# pad_2025-11-01.net
KiCad netlist of a schematic drawn in EasyEDA Pro
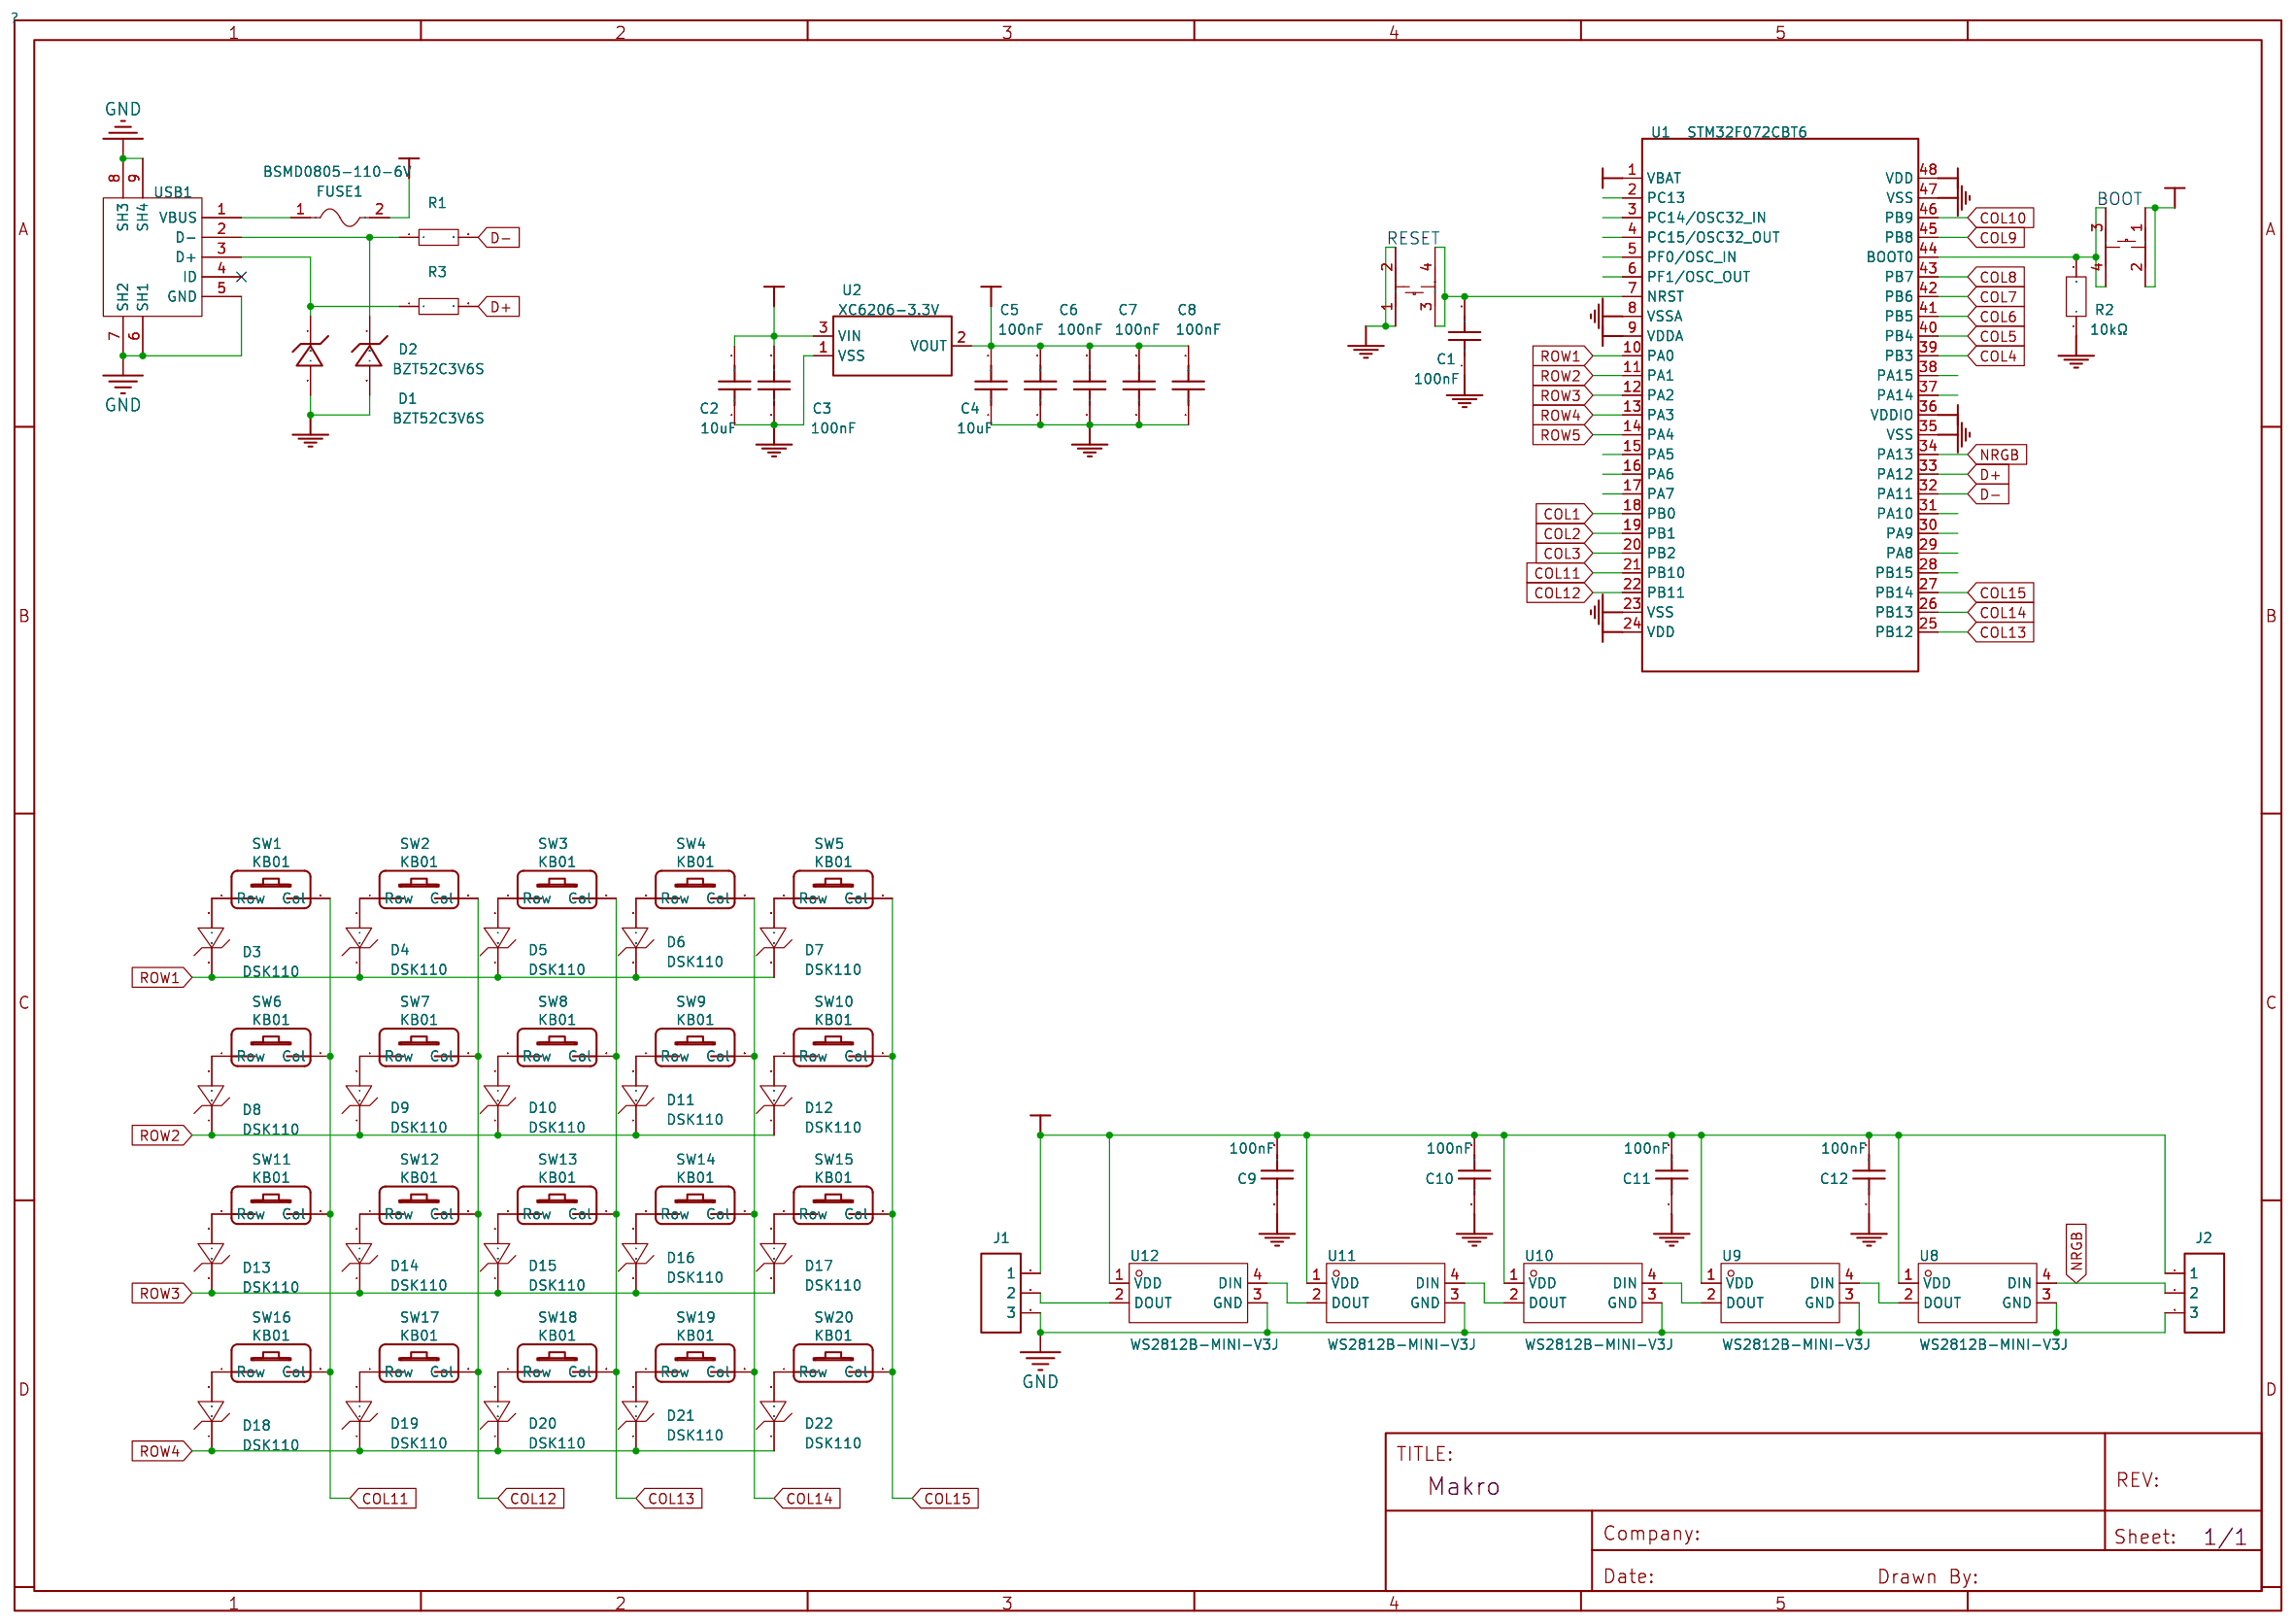
[diagram p0: schematic sheet]

(export (version "E")
  (design (tool "Eeschema 10.0.6"))
  (components
    (comp (ref "C1")
      (value "100nF")
      (fields
        (field (name "Manufacturer Part") "CC0805KKX7R0BB104")
        (field (name "Manufacturer") "YAGEO(国巨)")
      )
      (libsource (lib "easyedapro") (part "0.1uF"))
    )
    (comp (ref "C2")
      (value "10uF")
      (description "Capacitance:10uF Tolerance:±10% Tolerance:±10% Voltage Rating:6.3V Temperature Coefficient:X7R")
      (fields
        (field (name "Manufacturer Part") "CL21B106KQQNNNE")
        (field (name "Manufacturer") "SAMSUNG(三星)")
      )
      (libsource (lib "easyedapro") (part "10u"))
    )
    (comp (ref "C3")
      (value "100nF")
      (fields
        (field (name "Manufacturer Part") "CC0805KKX7R0BB104")
        (field (name "Manufacturer") "YAGEO(国巨)")
      )
      (libsource (lib "") (part "0.1uF_1"))
    )
    (comp (ref "C4")
      (value "10uF")
      (description "Capacitance:10uF Tolerance:±10% Tolerance:±10% Voltage Rating:6.3V Temperature Coefficient:X7R")
      (fields
        (field (name "Manufacturer Part") "CL21B106KQQNNNE")
        (field (name "Manufacturer") "SAMSUNG(三星)")
      )
      (libsource (lib "easyedapro") (part "10u"))
    )
    (comp (ref "C5")
      (value "100nF")
      (fields
        (field (name "Manufacturer Part") "CC0805KKX7R0BB104")
        (field (name "Manufacturer") "YAGEO(国巨)")
      )
      (libsource (lib "") (part "0.1uF_1"))
    )
    (comp (ref "C6")
      (value "100nF")
      (fields
        (field (name "Manufacturer Part") "CC0805KKX7R0BB104")
        (field (name "Manufacturer") "YAGEO(国巨)")
      )
      (libsource (lib "") (part "0.1uF_1"))
    )
    (comp (ref "C7")
      (value "100nF")
      (fields
        (field (name "Manufacturer Part") "CC0805KKX7R0BB104")
        (field (name "Manufacturer") "YAGEO(国巨)")
      )
      (libsource (lib "") (part "0.1uF_1"))
    )
    (comp (ref "C8")
      (value "100nF")
      (fields
        (field (name "Manufacturer Part") "CC0805KKX7R0BB104")
        (field (name "Manufacturer") "YAGEO(国巨)")
      )
      (libsource (lib "") (part "0.1uF_1"))
    )
    (comp (ref "C9")
      (value "100nF")
      (fields
        (field (name "Manufacturer Part") "CC0805KKX7R0BB104")
        (field (name "Manufacturer") "YAGEO(国巨)")
      )
      (libsource (lib "easyedapro") (part "0.1uF"))
    )
    (comp (ref "C10")
      (value "100nF")
      (fields
        (field (name "Manufacturer Part") "CC0805KKX7R0BB104")
        (field (name "Manufacturer") "YAGEO(国巨)")
      )
      (libsource (lib "easyedapro") (part "0.1uF"))
    )
    (comp (ref "C11")
      (value "100nF")
      (fields
        (field (name "Manufacturer Part") "CC0805KKX7R0BB104")
        (field (name "Manufacturer") "YAGEO(国巨)")
      )
      (libsource (lib "easyedapro") (part "0.1uF"))
    )
    (comp (ref "C12")
      (value "100nF")
      (fields
        (field (name "Manufacturer Part") "CC0805KKX7R0BB104")
        (field (name "Manufacturer") "YAGEO(国巨)")
      )
      (libsource (lib "easyedapro") (part "0.1uF"))
    )
    (comp (ref "D1")
      (value "BZT52C3V6S")
      (fields (field (name "Manufacturer") "CBI(创基)"))
      (libsource (lib "easyedapro") (part "ZMM3V6"))
    )
    (comp (ref "D2")
      (value "BZT52C3V6S")
      (fields (field (name "Manufacturer") "CBI(创基)"))
      (libsource (lib "easyedapro") (part "ZMM3V6"))
    )
    (comp (ref "D3")
      (value "DSK110")
      (footprint "easyedapro:SOD-123FL_L2.7-W1.8-LS3.8-RD")
      (fields (field (name "Manufacturer") "GOODWORK(固得沃克)"))
      (libsource (lib "easyedapro") (part "DSK110_C41371069"))
    )
    (comp (ref "D4")
      (value "DSK110")
      (footprint "easyedapro:SOD-123FL_L2.7-W1.8-LS3.8-RD")
      (fields (field (name "Manufacturer") "GOODWORK(固得沃克)"))
      (libsource (lib "easyedapro") (part "DSK110_C41371069"))
    )
    (comp (ref "D5")
      (value "DSK110")
      (footprint "easyedapro:SOD-123FL_L2.7-W1.8-LS3.8-RD")
      (fields (field (name "Manufacturer") "GOODWORK(固得沃克)"))
      (libsource (lib "easyedapro") (part "DSK110_C41371069"))
    )
    (comp (ref "D6")
      (value "DSK110")
      (footprint "easyedapro:SOD-123FL_L2.7-W1.8-LS3.8-RD")
      (fields (field (name "Manufacturer") "GOODWORK(固得沃克)"))
      (libsource (lib "easyedapro") (part "DSK110_C41371069"))
    )
    (comp (ref "D7")
      (value "DSK110")
      (footprint "easyedapro:SOD-123FL_L2.7-W1.8-LS3.8-RD")
      (fields (field (name "Manufacturer") "GOODWORK(固得沃克)"))
      (libsource (lib "easyedapro") (part "DSK110_C41371069"))
    )
    (comp (ref "D8")
      (value "DSK110")
      (footprint "easyedapro:SOD-123FL_L2.7-W1.8-LS3.8-RD")
      (fields (field (name "Manufacturer") "GOODWORK(固得沃克)"))
      (libsource (lib "easyedapro") (part "DSK110_C41371069"))
    )
    (comp (ref "D9")
      (value "DSK110")
      (footprint "easyedapro:SOD-123FL_L2.7-W1.8-LS3.8-RD")
      (fields (field (name "Manufacturer") "GOODWORK(固得沃克)"))
      (libsource (lib "easyedapro") (part "DSK110_C41371069"))
    )
    (comp (ref "D10")
      (value "DSK110")
      (footprint "easyedapro:SOD-123FL_L2.7-W1.8-LS3.8-RD")
      (fields (field (name "Manufacturer") "GOODWORK(固得沃克)"))
      (libsource (lib "easyedapro") (part "DSK110_C41371069"))
    )
    (comp (ref "D11")
      (value "DSK110")
      (footprint "easyedapro:SOD-123FL_L2.7-W1.8-LS3.8-RD")
      (fields (field (name "Manufacturer") "GOODWORK(固得沃克)"))
      (libsource (lib "easyedapro") (part "DSK110_C41371069"))
    )
    (comp (ref "D12")
      (value "DSK110")
      (footprint "easyedapro:SOD-123FL_L2.7-W1.8-LS3.8-RD")
      (fields (field (name "Manufacturer") "GOODWORK(固得沃克)"))
      (libsource (lib "easyedapro") (part "DSK110_C41371069"))
    )
    (comp (ref "D13")
      (value "DSK110")
      (footprint "easyedapro:SOD-123FL_L2.7-W1.8-LS3.8-RD")
      (fields (field (name "Manufacturer") "GOODWORK(固得沃克)"))
      (libsource (lib "easyedapro") (part "DSK110_C41371069"))
    )
    (comp (ref "D14")
      (value "DSK110")
      (footprint "easyedapro:SOD-123FL_L2.7-W1.8-LS3.8-RD")
      (fields (field (name "Manufacturer") "GOODWORK(固得沃克)"))
      (libsource (lib "easyedapro") (part "DSK110_C41371069"))
    )
    (comp (ref "D15")
      (value "DSK110")
      (footprint "easyedapro:SOD-123FL_L2.7-W1.8-LS3.8-RD")
      (fields (field (name "Manufacturer") "GOODWORK(固得沃克)"))
      (libsource (lib "easyedapro") (part "DSK110_C41371069"))
    )
    (comp (ref "D16")
      (value "DSK110")
      (footprint "easyedapro:SOD-123FL_L2.7-W1.8-LS3.8-RD")
      (fields (field (name "Manufacturer") "GOODWORK(固得沃克)"))
      (libsource (lib "easyedapro") (part "DSK110_C41371069"))
    )
    (comp (ref "D17")
      (value "DSK110")
      (footprint "easyedapro:SOD-123FL_L2.7-W1.8-LS3.8-RD")
      (fields (field (name "Manufacturer") "GOODWORK(固得沃克)"))
      (libsource (lib "easyedapro") (part "DSK110_C41371069"))
    )
    (comp (ref "D18")
      (value "DSK110")
      (footprint "easyedapro:SOD-123FL_L2.7-W1.8-LS3.8-RD")
      (fields (field (name "Manufacturer") "GOODWORK(固得沃克)"))
      (libsource (lib "easyedapro") (part "DSK110_C41371069"))
    )
    (comp (ref "D19")
      (value "DSK110")
      (footprint "easyedapro:SOD-123FL_L2.7-W1.8-LS3.8-RD")
      (fields (field (name "Manufacturer") "GOODWORK(固得沃克)"))
      (libsource (lib "easyedapro") (part "DSK110_C41371069"))
    )
    (comp (ref "D20")
      (value "DSK110")
      (footprint "easyedapro:SOD-123FL_L2.7-W1.8-LS3.8-RD")
      (fields (field (name "Manufacturer") "GOODWORK(固得沃克)"))
      (libsource (lib "easyedapro") (part "DSK110_C41371069"))
    )
    (comp (ref "D21")
      (value "DSK110")
      (footprint "easyedapro:SOD-123FL_L2.7-W1.8-LS3.8-RD")
      (fields (field (name "Manufacturer") "GOODWORK(固得沃克)"))
      (libsource (lib "easyedapro") (part "DSK110_C41371069"))
    )
    (comp (ref "D22")
      (value "DSK110")
      (footprint "easyedapro:SOD-123FL_L2.7-W1.8-LS3.8-RD")
      (fields (field (name "Manufacturer") "GOODWORK(固得沃克)"))
      (libsource (lib "easyedapro") (part "DSK110_C41371069"))
    )
    (comp (ref "FUSE1")
      (value "BSMD0805-110-6V")
      (footprint "easyedapro:F0805")
      (fields (field (name "Manufacturer") "BHFUSE(佰宏)"))
      (libsource (lib "easyedapro") (part "BSMD0805-110-6V"))
    )
    (comp (ref "J1") (value "77311-102-03LF") (libsource (lib "") (part "Pin03_1")))
    (comp (ref "J2") (value "77311-102-03LF") (libsource (lib "easyedapro") (part "Pin03")))
    (comp (ref "KEY1")
      (value "TS-1187A-C-B-B")
      (footprint "easyedapro:SW-SMD_4P-L5.1-W5.1-P3.70-LS6.5-TL_H1.6")
      (fields (field (name "Manufacturer") "XKB Connectivity(中国星坤)"))
      (libsource (lib "easyedapro") (part "TS-1187A-C-B-B"))
    )
    (comp (ref "KEY2")
      (value "TS-1187A-C-B-B")
      (footprint "easyedapro:SW-SMD_4P-L5.1-W5.1-P3.70-LS6.5-TL_H1.6")
      (fields (field (name "Manufacturer") "XKB Connectivity(中国星坤)"))
      (libsource (lib "easyedapro") (part "TS-1187A-C-B-B"))
    )
    (comp (ref "R1")
      (value "22Ω")
      (footprint "easyedapro:R0805")
      (fields
        (field (name "Manufacturer Part") "0805W8F220JT5E")
        (field (name "Manufacturer") "UNI-ROYAL(厚声)")
      )
      (libsource (lib "easyedapro") (part "0805W8F220JT5E"))
    )
    (comp (ref "R2")
      (value "10kΩ")
      (footprint "easyedapro:R0805")
      (fields (field (name "Manufacturer Part") "FRC0805J103TS") (field (name "Manufacturer") "FOJAN(富捷)"))
      (libsource (lib "easyedapro") (part "FRC0805J103TS"))
    )
    (comp (ref "R3")
      (value "22Ω")
      (footprint "easyedapro:R0805")
      (fields
        (field (name "Manufacturer Part") "0805W8F220JT5E")
        (field (name "Manufacturer") "UNI-ROYAL(厚声)")
      )
      (libsource (lib "easyedapro") (part "0805W8F220JT5E"))
    )
    (comp (ref "SW1")
      (value "KB01")
      (fields (field (name "Manufacturer Part") "00") (field (name "Contributor") "Citiclzy"))
      (libsource (lib "easyedapro") (part "KB01"))
    )
    (comp (ref "SW2")
      (value "KB01")
      (fields (field (name "Manufacturer Part") "00") (field (name "Contributor") "Citiclzy"))
      (libsource (lib "easyedapro") (part "KB01"))
    )
    (comp (ref "SW3")
      (value "KB01")
      (fields (field (name "Manufacturer Part") "00") (field (name "Contributor") "Citiclzy"))
      (libsource (lib "easyedapro") (part "KB01"))
    )
    (comp (ref "SW4")
      (value "KB01")
      (fields (field (name "Manufacturer Part") "00") (field (name "Contributor") "Citiclzy"))
      (libsource (lib "easyedapro") (part "KB01"))
    )
    (comp (ref "SW5")
      (value "KB01")
      (fields (field (name "Manufacturer Part") "00") (field (name "Contributor") "Citiclzy"))
      (libsource (lib "easyedapro") (part "KB01"))
    )
    (comp (ref "SW6")
      (value "KB01")
      (fields (field (name "Manufacturer Part") "00") (field (name "Contributor") "Citiclzy"))
      (libsource (lib "easyedapro") (part "KB01"))
    )
    (comp (ref "SW7")
      (value "KB01")
      (fields (field (name "Manufacturer Part") "00") (field (name "Contributor") "Citiclzy"))
      (libsource (lib "easyedapro") (part "KB01"))
    )
    (comp (ref "SW8")
      (value "KB01")
      (fields (field (name "Manufacturer Part") "00") (field (name "Contributor") "Citiclzy"))
      (libsource (lib "easyedapro") (part "KB01"))
    )
    (comp (ref "SW9")
      (value "KB01")
      (fields (field (name "Manufacturer Part") "00") (field (name "Contributor") "Citiclzy"))
      (libsource (lib "easyedapro") (part "KB01"))
    )
    (comp (ref "SW10")
      (value "KB01")
      (fields (field (name "Manufacturer Part") "00") (field (name "Contributor") "Citiclzy"))
      (libsource (lib "easyedapro") (part "KB01"))
    )
    (comp (ref "SW11")
      (value "KB01")
      (fields (field (name "Manufacturer Part") "00") (field (name "Contributor") "Citiclzy"))
      (libsource (lib "easyedapro") (part "KB01"))
    )
    (comp (ref "SW12")
      (value "KB01")
      (fields (field (name "Manufacturer Part") "00") (field (name "Contributor") "Citiclzy"))
      (libsource (lib "easyedapro") (part "KB01"))
    )
    (comp (ref "SW13")
      (value "KB01")
      (fields (field (name "Manufacturer Part") "00") (field (name "Contributor") "Citiclzy"))
      (libsource (lib "easyedapro") (part "KB01"))
    )
    (comp (ref "SW14")
      (value "KB01")
      (fields (field (name "Manufacturer Part") "00") (field (name "Contributor") "Citiclzy"))
      (libsource (lib "easyedapro") (part "KB01"))
    )
    (comp (ref "SW15")
      (value "KB01")
      (fields (field (name "Manufacturer Part") "00") (field (name "Contributor") "Citiclzy"))
      (libsource (lib "easyedapro") (part "KB01"))
    )
    (comp (ref "SW16")
      (value "KB01")
      (fields (field (name "Manufacturer Part") "00") (field (name "Contributor") "Citiclzy"))
      (libsource (lib "easyedapro") (part "KB01"))
    )
    (comp (ref "SW17")
      (value "KB01")
      (fields (field (name "Manufacturer Part") "00") (field (name "Contributor") "Citiclzy"))
      (libsource (lib "easyedapro") (part "KB01"))
    )
    (comp (ref "SW18")
      (value "KB01")
      (fields (field (name "Manufacturer Part") "00") (field (name "Contributor") "Citiclzy"))
      (libsource (lib "easyedapro") (part "KB01"))
    )
    (comp (ref "SW19")
      (value "KB01")
      (fields (field (name "Manufacturer Part") "00") (field (name "Contributor") "Citiclzy"))
      (libsource (lib "easyedapro") (part "KB01"))
    )
    (comp (ref "SW20")
      (value "KB01")
      (fields (field (name "Manufacturer Part") "00") (field (name "Contributor") "Citiclzy"))
      (libsource (lib "easyedapro") (part "KB01"))
    )
    (comp (ref "U1")
      (value "STM32F072CBT6")
      (footprint "easyedapro:LQFP-48_L7.0-W7.0-P0.50-LS9.0-BL")
      (fields (field (name "Manufacturer") "ST(意法半导体)"))
      (libsource (lib "easyedapro") (part "STM32F072CBT6"))
    )
    (comp (ref "U2")
      (value "XC6206-3.3V")
      (footprint "easyedapro:SSOT-3_L2.9-W1.6-P0.95-LS2.8-BR")
      (fields (field (name "Manufacturer") "YONGYUTAI(永裕泰)") (field (name "Contributor") "LCSC"))
      (libsource (lib "easyedapro") (part "XC6206-3.3V"))
    )
    (comp (ref "U8")
      (value "WS2812B-MINI-V3J")
      (footprint "easyedapro:LED-SMD_4P-L3.5-W3.5-P1.80-LS6.2_WS2812B-MINI-V3J")
      (fields (field (name "Manufacturer") "worldsemi"))
      (libsource (lib "easyedapro") (part "WS2812B-MINI-V3J"))
    )
    (comp (ref "U9")
      (value "WS2812B-MINI-V3J")
      (footprint "easyedapro:LED-SMD_4P-L3.5-W3.5-P1.80-LS6.2_WS2812B-MINI-V3J")
      (fields (field (name "Manufacturer") "worldsemi"))
      (libsource (lib "easyedapro") (part "WS2812B-MINI-V3J"))
    )
    (comp (ref "U10")
      (value "WS2812B-MINI-V3J")
      (footprint "easyedapro:LED-SMD_4P-L3.5-W3.5-P1.80-LS6.2_WS2812B-MINI-V3J")
      (fields (field (name "Manufacturer") "worldsemi"))
      (libsource (lib "easyedapro") (part "WS2812B-MINI-V3J"))
    )
    (comp (ref "U11")
      (value "WS2812B-MINI-V3J")
      (footprint "easyedapro:LED-SMD_4P-L3.5-W3.5-P1.80-LS6.2_WS2812B-MINI-V3J")
      (fields (field (name "Manufacturer") "worldsemi"))
      (libsource (lib "easyedapro") (part "WS2812B-MINI-V3J"))
    )
    (comp (ref "U12")
      (value "WS2812B-MINI-V3J")
      (footprint "easyedapro:LED-SMD_4P-L3.5-W3.5-P1.80-LS6.2_WS2812B-MINI-V3J")
      (fields (field (name "Manufacturer") "worldsemi"))
      (libsource (lib "easyedapro") (part "WS2812B-MINI-V3J"))
    )
    (comp (ref "USB1")
      (value "MicroXNJ")
      (footprint "easyedapro:MICRO-USB-SMD_MICROXNJ")
      (fields (field (name "Manufacturer") "SHOU HAN(首韩)"))
      (libsource (lib "easyedapro") (part "MICROXNJ"))
    )
  )
  (nets
    (net (code "1") (name "+3.3V") (class "Default")
      (node (ref "C4") (pin "2") (pinfunction "2_2") (pintype "unspecified"))
      (node (ref "C5") (pin "2") (pinfunction "2_2") (pintype "unspecified"))
      (node (ref "C6") (pin "2") (pinfunction "2_2") (pintype "unspecified"))
      (node (ref "C7") (pin "2") (pinfunction "2_2") (pintype "unspecified"))
      (node (ref "C8") (pin "2") (pinfunction "2_2") (pintype "unspecified"))
      (node (ref "KEY1") (pin "1") (pinfunction "1_1") (pintype "unspecified"))
      (node (ref "KEY1") (pin "2") (pinfunction "2_2") (pintype "unspecified"))
      (node (ref "U1") (pin "1") (pinfunction "VBAT_1") (pintype "unspecified"))
      (node (ref "U1") (pin "24") (pinfunction "VDD_24") (pintype "unspecified"))
      (node (ref "U1") (pin "36") (pinfunction "VDDIO_36") (pintype "unspecified"))
      (node (ref "U1") (pin "48") (pinfunction "VDD_48") (pintype "unspecified"))
      (node (ref "U1") (pin "9") (pinfunction "VDDA_9") (pintype "unspecified"))
      (node (ref "U2") (pin "2") (pinfunction "VOUT_2") (pintype "unspecified"))
    )
    (net (code "2") (name "COL1") (class "Default")
      (node (ref "U1") (pin "18") (pinfunction "PB0_18") (pintype "unspecified"))
    )
    (net (code "3") (name "COL2") (class "Default")
      (node (ref "U1") (pin "19") (pinfunction "PB1_19") (pintype "unspecified"))
    )
    (net (code "4") (name "COL3") (class "Default")
      (node (ref "U1") (pin "20") (pinfunction "PB2_20") (pintype "unspecified"))
    )
    (net (code "5") (name "COL4") (class "Default")
      (node (ref "U1") (pin "39") (pinfunction "PB3_39") (pintype "unspecified"))
    )
    (net (code "6") (name "COL5") (class "Default")
      (node (ref "U1") (pin "40") (pinfunction "PB4_40") (pintype "unspecified"))
    )
    (net (code "7") (name "COL6") (class "Default")
      (node (ref "U1") (pin "41") (pinfunction "PB5_41") (pintype "unspecified"))
    )
    (net (code "8") (name "COL7") (class "Default")
      (node (ref "U1") (pin "42") (pinfunction "PB6_42") (pintype "unspecified"))
    )
    (net (code "9") (name "COL8") (class "Default")
      (node (ref "U1") (pin "43") (pinfunction "PB7_43") (pintype "unspecified"))
    )
    (net (code "10") (name "COL9") (class "Default")
      (node (ref "U1") (pin "45") (pinfunction "PB8_45") (pintype "unspecified"))
    )
    (net (code "11") (name "COL10") (class "Default")
      (node (ref "U1") (pin "46") (pinfunction "PB9_46") (pintype "unspecified"))
    )
    (net (code "12") (name "COL11") (class "Default")
      (node (ref "SW1") (pin "2") (pinfunction "Col_2") (pintype "unspecified"))
      (node (ref "SW11") (pin "2") (pinfunction "Col_2") (pintype "unspecified"))
      (node (ref "SW16") (pin "2") (pinfunction "Col_2") (pintype "unspecified"))
      (node (ref "SW6") (pin "2") (pinfunction "Col_2") (pintype "unspecified"))
      (node (ref "U1") (pin "21") (pinfunction "PB10_21") (pintype "unspecified"))
    )
    (net (code "13") (name "COL12") (class "Default")
      (node (ref "SW12") (pin "2") (pinfunction "Col_2") (pintype "unspecified"))
      (node (ref "SW17") (pin "2") (pinfunction "Col_2") (pintype "unspecified"))
      (node (ref "SW2") (pin "2") (pinfunction "Col_2") (pintype "unspecified"))
      (node (ref "SW7") (pin "2") (pinfunction "Col_2") (pintype "unspecified"))
      (node (ref "U1") (pin "22") (pinfunction "PB11_22") (pintype "unspecified"))
    )
    (net (code "14") (name "COL13") (class "Default")
      (node (ref "SW13") (pin "2") (pinfunction "Col_2") (pintype "unspecified"))
      (node (ref "SW18") (pin "2") (pinfunction "Col_2") (pintype "unspecified"))
      (node (ref "SW3") (pin "2") (pinfunction "Col_2") (pintype "unspecified"))
      (node (ref "SW8") (pin "2") (pinfunction "Col_2") (pintype "unspecified"))
      (node (ref "U1") (pin "25") (pinfunction "PB12_25") (pintype "unspecified"))
    )
    (net (code "15") (name "COL14") (class "Default")
      (node (ref "SW14") (pin "2") (pinfunction "Col_2") (pintype "unspecified"))
      (node (ref "SW19") (pin "2") (pinfunction "Col_2") (pintype "unspecified"))
      (node (ref "SW4") (pin "2") (pinfunction "Col_2") (pintype "unspecified"))
      (node (ref "SW9") (pin "2") (pinfunction "Col_2") (pintype "unspecified"))
      (node (ref "U1") (pin "26") (pinfunction "PB13_26") (pintype "unspecified"))
    )
    (net (code "16") (name "COL15") (class "Default")
      (node (ref "SW10") (pin "2") (pinfunction "Col_2") (pintype "unspecified"))
      (node (ref "SW15") (pin "2") (pinfunction "Col_2") (pintype "unspecified"))
      (node (ref "SW20") (pin "2") (pinfunction "Col_2") (pintype "unspecified"))
      (node (ref "SW5") (pin "2") (pinfunction "Col_2") (pintype "unspecified"))
      (node (ref "U1") (pin "27") (pinfunction "PB14_27") (pintype "unspecified"))
    )
    (net (code "17") (name "D+") (class "Default")
      (node (ref "R3") (pin "2") (pinfunction "2_2") (pintype "input"))
      (node (ref "U1") (pin "33") (pinfunction "PA12_33") (pintype "unspecified"))
    )
    (net (code "18") (name "D-") (class "Default")
      (node (ref "R1") (pin "2") (pinfunction "2_2") (pintype "input"))
      (node (ref "U1") (pin "32") (pinfunction "PA11_32") (pintype "unspecified"))
    )
    (net (code "19") (name "GND") (class "Default")
      (node (ref "C1") (pin "1") (pinfunction "1_1") (pintype "unspecified"))
      (node (ref "C10") (pin "1") (pinfunction "1_1") (pintype "unspecified"))
      (node (ref "C11") (pin "1") (pinfunction "1_1") (pintype "unspecified"))
      (node (ref "C12") (pin "1") (pinfunction "1_1") (pintype "unspecified"))
      (node (ref "C2") (pin "1") (pinfunction "1_1") (pintype "unspecified"))
      (node (ref "C3") (pin "1") (pinfunction "1_1") (pintype "unspecified"))
      (node (ref "C4") (pin "1") (pinfunction "1_1") (pintype "unspecified"))
      (node (ref "C5") (pin "1") (pinfunction "1_1") (pintype "unspecified"))
      (node (ref "C6") (pin "1") (pinfunction "1_1") (pintype "unspecified"))
      (node (ref "C7") (pin "1") (pinfunction "1_1") (pintype "unspecified"))
      (node (ref "C8") (pin "1") (pinfunction "1_1") (pintype "unspecified"))
      (node (ref "C9") (pin "1") (pinfunction "1_1") (pintype "unspecified"))
      (node (ref "D1") (pin "2") (pinfunction "A_2") (pintype "unspecified"))
      (node (ref "D2") (pin "2") (pinfunction "A_2") (pintype "unspecified"))
      (node (ref "J1") (pin "3") (pinfunction "3_3") (pintype "input"))
      (node (ref "J2") (pin "3") (pinfunction "3_3") (pintype "input"))
      (node (ref "KEY2") (pin "1") (pinfunction "1_1") (pintype "unspecified"))
      (node (ref "KEY2") (pin "2") (pinfunction "2_2") (pintype "unspecified"))
      (node (ref "R2") (pin "1") (pinfunction "1_1") (pintype "unspecified"))
      (node (ref "U1") (pin "23") (pinfunction "VSS_23") (pintype "unspecified"))
      (node (ref "U1") (pin "35") (pinfunction "VSS_35") (pintype "unspecified"))
      (node (ref "U1") (pin "47") (pinfunction "VSS_47") (pintype "unspecified"))
      (node (ref "U1") (pin "8") (pinfunction "VSSA_8") (pintype "unspecified"))
      (node (ref "U10") (pin "3") (pinfunction "GND_3") (pintype "unspecified"))
      (node (ref "U11") (pin "3") (pinfunction "GND_3") (pintype "unspecified"))
      (node (ref "U12") (pin "3") (pinfunction "GND_3") (pintype "unspecified"))
      (node (ref "U2") (pin "1") (pinfunction "VSS_1") (pintype "unspecified"))
      (node (ref "U8") (pin "3") (pinfunction "GND_3") (pintype "unspecified"))
      (node (ref "U9") (pin "3") (pinfunction "GND_3") (pintype "unspecified"))
      (node (ref "USB1") (pin "5") (pinfunction "GND_5") (pintype "unspecified"))
      (node (ref "USB1") (pin "6") (pinfunction "SH1_6") (pintype "unspecified"))
      (node (ref "USB1") (pin "7") (pinfunction "SH2_7") (pintype "unspecified"))
      (node (ref "USB1") (pin "8") (pinfunction "SH3_8") (pintype "unspecified"))
      (node (ref "USB1") (pin "9") (pinfunction "SH4_9") (pintype "unspecified"))
    )
    (net (code "20") (name "NRGB") (class "Default")
      (node (ref "J2") (pin "2") (pinfunction "2_2") (pintype "input"))
      (node (ref "U1") (pin "34") (pinfunction "PA13_34") (pintype "unspecified"))
      (node (ref "U8") (pin "4") (pinfunction "DIN_4") (pintype "unspecified"))
    )
    (net (code "21") (name "Net-(D1-C)") (class "Default")
      (node (ref "D1") (pin "1") (pinfunction "C_1") (pintype "unspecified"))
      (node (ref "R3") (pin "1") (pinfunction "1_1") (pintype "input"))
      (node (ref "USB1") (pin "3") (pinfunction "D+_3") (pintype "unspecified"))
    )
    (net (code "22") (name "Net-(D2-C)") (class "Default")
      (node (ref "D2") (pin "1") (pinfunction "C_1") (pintype "unspecified"))
      (node (ref "R1") (pin "1") (pinfunction "1_1") (pintype "input"))
      (node (ref "USB1") (pin "2") (pinfunction "D-_2") (pintype "unspecified"))
    )
    (net (code "23") (name "Net-(D3-A)") (class "Default")
      (node (ref "D3") (pin "2") (pinfunction "A_2") (pintype "unspecified"))
      (node (ref "SW1") (pin "1") (pinfunction "Row_1") (pintype "unspecified"))
    )
    (net (code "24") (name "Net-(D4-A)") (class "Default")
      (node (ref "D4") (pin "2") (pinfunction "A_2") (pintype "unspecified"))
      (node (ref "SW2") (pin "1") (pinfunction "Row_1") (pintype "unspecified"))
    )
    (net (code "25") (name "Net-(D5-A)") (class "Default")
      (node (ref "D5") (pin "2") (pinfunction "A_2") (pintype "unspecified"))
      (node (ref "SW3") (pin "1") (pinfunction "Row_1") (pintype "unspecified"))
    )
    (net (code "26") (name "Net-(D6-A)") (class "Default")
      (node (ref "D6") (pin "2") (pinfunction "A_2") (pintype "unspecified"))
      (node (ref "SW4") (pin "1") (pinfunction "Row_1") (pintype "unspecified"))
    )
    (net (code "27") (name "Net-(D7-A)") (class "Default")
      (node (ref "D7") (pin "2") (pinfunction "A_2") (pintype "unspecified"))
      (node (ref "SW5") (pin "1") (pinfunction "Row_1") (pintype "unspecified"))
    )
    (net (code "28") (name "Net-(D8-A)") (class "Default")
      (node (ref "D8") (pin "2") (pinfunction "A_2") (pintype "unspecified"))
      (node (ref "SW6") (pin "1") (pinfunction "Row_1") (pintype "unspecified"))
    )
    (net (code "29") (name "Net-(D9-A)") (class "Default")
      (node (ref "D9") (pin "2") (pinfunction "A_2") (pintype "unspecified"))
      (node (ref "SW7") (pin "1") (pinfunction "Row_1") (pintype "unspecified"))
    )
    (net (code "30") (name "Net-(D10-A)") (class "Default")
      (node (ref "D10") (pin "2") (pinfunction "A_2") (pintype "unspecified"))
      (node (ref "SW8") (pin "1") (pinfunction "Row_1") (pintype "unspecified"))
    )
    (net (code "31") (name "Net-(D11-A)") (class "Default")
      (node (ref "D11") (pin "2") (pinfunction "A_2") (pintype "unspecified"))
      (node (ref "SW9") (pin "1") (pinfunction "Row_1") (pintype "unspecified"))
    )
    (net (code "32") (name "Net-(D12-A)") (class "Default")
      (node (ref "D12") (pin "2") (pinfunction "A_2") (pintype "unspecified"))
      (node (ref "SW10") (pin "1") (pinfunction "Row_1") (pintype "unspecified"))
    )
    (net (code "33") (name "Net-(D13-A)") (class "Default")
      (node (ref "D13") (pin "2") (pinfunction "A_2") (pintype "unspecified"))
      (node (ref "SW11") (pin "1") (pinfunction "Row_1") (pintype "unspecified"))
    )
    (net (code "34") (name "Net-(D14-A)") (class "Default")
      (node (ref "D14") (pin "2") (pinfunction "A_2") (pintype "unspecified"))
      (node (ref "SW12") (pin "1") (pinfunction "Row_1") (pintype "unspecified"))
    )
    (net (code "35") (name "Net-(D15-A)") (class "Default")
      (node (ref "D15") (pin "2") (pinfunction "A_2") (pintype "unspecified"))
      (node (ref "SW13") (pin "1") (pinfunction "Row_1") (pintype "unspecified"))
    )
    (net (code "36") (name "Net-(D16-A)") (class "Default")
      (node (ref "D16") (pin "2") (pinfunction "A_2") (pintype "unspecified"))
      (node (ref "SW14") (pin "1") (pinfunction "Row_1") (pintype "unspecified"))
    )
    (net (code "37") (name "Net-(D17-A)") (class "Default")
      (node (ref "D17") (pin "2") (pinfunction "A_2") (pintype "unspecified"))
      (node (ref "SW15") (pin "1") (pinfunction "Row_1") (pintype "unspecified"))
    )
    (net (code "38") (name "Net-(D18-A)") (class "Default")
      (node (ref "D18") (pin "2") (pinfunction "A_2") (pintype "unspecified"))
      (node (ref "SW16") (pin "1") (pinfunction "Row_1") (pintype "unspecified"))
    )
    (net (code "39") (name "Net-(D19-A)") (class "Default")
      (node (ref "D19") (pin "2") (pinfunction "A_2") (pintype "unspecified"))
      (node (ref "SW17") (pin "1") (pinfunction "Row_1") (pintype "unspecified"))
    )
    (net (code "40") (name "Net-(D20-A)") (class "Default")
      (node (ref "D20") (pin "2") (pinfunction "A_2") (pintype "unspecified"))
      (node (ref "SW18") (pin "1") (pinfunction "Row_1") (pintype "unspecified"))
    )
    (net (code "41") (name "Net-(D21-A)") (class "Default")
      (node (ref "D21") (pin "2") (pinfunction "A_2") (pintype "unspecified"))
      (node (ref "SW19") (pin "1") (pinfunction "Row_1") (pintype "unspecified"))
    )
    (net (code "42") (name "Net-(D22-A)") (class "Default")
      (node (ref "D22") (pin "2") (pinfunction "A_2") (pintype "unspecified"))
      (node (ref "SW20") (pin "1") (pinfunction "Row_1") (pintype "unspecified"))
    )
    (net (code "43") (name "Net-(U1-BOOT0)") (class "Default")
      (node (ref "KEY1") (pin "3") (pinfunction "3_3") (pintype "unspecified"))
      (node (ref "KEY1") (pin "4") (pinfunction "4_4") (pintype "unspecified"))
      (node (ref "R2") (pin "2") (pinfunction "2_2") (pintype "unspecified"))
      (node (ref "U1") (pin "44") (pinfunction "BOOT0_44") (pintype "unspecified"))
    )
    (net (code "44") (name "Net-(U1-NRST)") (class "Default")
      (node (ref "C1") (pin "2") (pinfunction "2_2") (pintype "unspecified"))
      (node (ref "KEY2") (pin "3") (pinfunction "3_3") (pintype "unspecified"))
      (node (ref "KEY2") (pin "4") (pinfunction "4_4") (pintype "unspecified"))
      (node (ref "U1") (pin "7") (pinfunction "NRST_7") (pintype "unspecified"))
    )
    (net (code "45") (name "Net-(U8-DOUT)") (class "Default")
      (node (ref "U8") (pin "2") (pinfunction "DOUT_2") (pintype "unspecified"))
      (node (ref "U9") (pin "4") (pinfunction "DIN_4") (pintype "unspecified"))
    )
    (net (code "46") (name "Net-(U10-DIN)") (class "Default")
      (node (ref "U10") (pin "4") (pinfunction "DIN_4") (pintype "unspecified"))
      (node (ref "U9") (pin "2") (pinfunction "DOUT_2") (pintype "unspecified"))
    )
    (net (code "47") (name "Net-(U10-DOUT)") (class "Default")
      (node (ref "U10") (pin "2") (pinfunction "DOUT_2") (pintype "unspecified"))
      (node (ref "U11") (pin "4") (pinfunction "DIN_4") (pintype "unspecified"))
    )
    (net (code "48") (name "Net-(U11-DOUT)") (class "Default")
      (node (ref "U11") (pin "2") (pinfunction "DOUT_2") (pintype "unspecified"))
      (node (ref "U12") (pin "4") (pinfunction "DIN_4") (pintype "unspecified"))
    )
    (net (code "49") (name "Net-(U12-DOUT)") (class "Default")
      (node (ref "J1") (pin "2") (pinfunction "2_2") (pintype "input"))
      (node (ref "U12") (pin "2") (pinfunction "DOUT_2") (pintype "unspecified"))
    )
    (net (code "50") (name "Net-(USB1-VBUS)") (class "Default")
      (node (ref "FUSE1") (pin "1") (pinfunction "1_1") (pintype "input"))
      (node (ref "USB1") (pin "1") (pinfunction "VBUS_1") (pintype "unspecified"))
    )
    (net (code "51") (name "ROW1") (class "Default")
      (node (ref "D3") (pin "1") (pinfunction "C_1") (pintype "unspecified"))
      (node (ref "D4") (pin "1") (pinfunction "C_1") (pintype "unspecified"))
      (node (ref "D5") (pin "1") (pinfunction "C_1") (pintype "unspecified"))
      (node (ref "D6") (pin "1") (pinfunction "C_1") (pintype "unspecified"))
      (node (ref "D7") (pin "1") (pinfunction "C_1") (pintype "unspecified"))
      (node (ref "U1") (pin "10") (pinfunction "PA0_10") (pintype "unspecified"))
    )
    (net (code "52") (name "ROW2") (class "Default")
      (node (ref "D10") (pin "1") (pinfunction "C_1") (pintype "unspecified"))
      (node (ref "D11") (pin "1") (pinfunction "C_1") (pintype "unspecified"))
      (node (ref "D12") (pin "1") (pinfunction "C_1") (pintype "unspecified"))
      (node (ref "D8") (pin "1") (pinfunction "C_1") (pintype "unspecified"))
      (node (ref "D9") (pin "1") (pinfunction "C_1") (pintype "unspecified"))
      (node (ref "U1") (pin "11") (pinfunction "PA1_11") (pintype "unspecified"))
    )
    (net (code "53") (name "ROW3") (class "Default")
      (node (ref "D13") (pin "1") (pinfunction "C_1") (pintype "unspecified"))
      (node (ref "D14") (pin "1") (pinfunction "C_1") (pintype "unspecified"))
      (node (ref "D15") (pin "1") (pinfunction "C_1") (pintype "unspecified"))
      (node (ref "D16") (pin "1") (pinfunction "C_1") (pintype "unspecified"))
      (node (ref "D17") (pin "1") (pinfunction "C_1") (pintype "unspecified"))
      (node (ref "U1") (pin "12") (pinfunction "PA2_12") (pintype "unspecified"))
    )
    (net (code "54") (name "ROW4") (class "Default")
      (node (ref "D18") (pin "1") (pinfunction "C_1") (pintype "unspecified"))
      (node (ref "D19") (pin "1") (pinfunction "C_1") (pintype "unspecified"))
      (node (ref "D20") (pin "1") (pinfunction "C_1") (pintype "unspecified"))
      (node (ref "D21") (pin "1") (pinfunction "C_1") (pintype "unspecified"))
      (node (ref "D22") (pin "1") (pinfunction "C_1") (pintype "unspecified"))
      (node (ref "U1") (pin "13") (pinfunction "PA3_13") (pintype "unspecified"))
    )
    (net (code "55") (name "ROW5") (class "Default")
      (node (ref "U1") (pin "14") (pinfunction "PA4_14") (pintype "unspecified"))
    )
    (net (code "56") (name "VCC") (class "Default")
      (node (ref "C10") (pin "2") (pinfunction "2_2") (pintype "unspecified"))
      (node (ref "C11") (pin "2") (pinfunction "2_2") (pintype "unspecified"))
      (node (ref "C12") (pin "2") (pinfunction "2_2") (pintype "unspecified"))
      (node (ref "C2") (pin "2") (pinfunction "2_2") (pintype "unspecified"))
      (node (ref "C3") (pin "2") (pinfunction "2_2") (pintype "unspecified"))
      (node (ref "C9") (pin "2") (pinfunction "2_2") (pintype "unspecified"))
      (node (ref "FUSE1") (pin "2") (pinfunction "2_2") (pintype "input"))
      (node (ref "J1") (pin "1") (pinfunction "1_1") (pintype "input"))
      (node (ref "J2") (pin "1") (pinfunction "1_1") (pintype "input"))
      (node (ref "U10") (pin "1") (pinfunction "VDD_1") (pintype "unspecified"))
      (node (ref "U11") (pin "1") (pinfunction "VDD_1") (pintype "unspecified"))
      (node (ref "U12") (pin "1") (pinfunction "VDD_1") (pintype "unspecified"))
      (node (ref "U2") (pin "3") (pinfunction "VIN_3") (pintype "unspecified"))
      (node (ref "U8") (pin "1") (pinfunction "VDD_1") (pintype "unspecified"))
      (node (ref "U9") (pin "1") (pinfunction "VDD_1") (pintype "unspecified"))
    )
    (net (code "57") (name "unconnected-(U1-PA5-Pad15)") (class "Default")
      (node (ref "U1") (pin "15") (pinfunction "PA5_15") (pintype "unspecified"))
    )
    (net (code "58") (name "unconnected-(U1-PA6-Pad16)") (class "Default")
      (node (ref "U1") (pin "16") (pinfunction "PA6_16") (pintype "unspecified"))
    )
    (net (code "59") (name "unconnected-(U1-PA7-Pad17)") (class "Default")
      (node (ref "U1") (pin "17") (pinfunction "PA7_17") (pintype "unspecified"))
    )
    (net (code "60") (name "unconnected-(U1-PA8-Pad29)") (class "Default")
      (node (ref "U1") (pin "29") (pinfunction "PA8_29") (pintype "unspecified"))
    )
    (net (code "61") (name "unconnected-(U1-PA9-Pad30)") (class "Default")
      (node (ref "U1") (pin "30") (pinfunction "PA9_30") (pintype "unspecified"))
    )
    (net (code "62") (name "unconnected-(U1-PA10-Pad31)") (class "Default")
      (node (ref "U1") (pin "31") (pinfunction "PA10_31") (pintype "unspecified"))
    )
    (net (code "63") (name "unconnected-(U1-PA14-Pad37)") (class "Default")
      (node (ref "U1") (pin "37") (pinfunction "PA14_37") (pintype "unspecified"))
    )
    (net (code "64") (name "unconnected-(U1-PA15-Pad38)") (class "Default")
      (node (ref "U1") (pin "38") (pinfunction "PA15_38") (pintype "unspecified"))
    )
    (net (code "65") (name "unconnected-(U1-PB15-Pad28)") (class "Default")
      (node (ref "U1") (pin "28") (pinfunction "PB15_28") (pintype "unspecified"))
    )
    (net (code "66") (name "unconnected-(U1-PC13-Pad2)") (class "Default")
      (node (ref "U1") (pin "2") (pinfunction "PC13_2") (pintype "unspecified"))
    )
    (net (code "67") (name "unconnected-(U1-PC14{slash}OSC32_IN-Pad3)") (class "Default")
      (node (ref "U1") (pin "3") (pinfunction "PC14/OSC32_IN_3") (pintype "unspecified"))
    )
    (net (code "68") (name "unconnected-(U1-PC15{slash}OSC32_OUT-Pad4)") (class "Default")
      (node (ref "U1") (pin "4") (pinfunction "PC15/OSC32_OUT_4") (pintype "unspecified"))
    )
    (net (code "69") (name "unconnected-(U1-PF0{slash}OSC_IN-Pad5)") (class "Default")
      (node (ref "U1") (pin "5") (pinfunction "PF0/OSC_IN_5") (pintype "unspecified"))
    )
    (net (code "70") (name "unconnected-(U1-PF1{slash}OSC_OUT-Pad6)") (class "Default")
      (node (ref "U1") (pin "6") (pinfunction "PF1/OSC_OUT_6") (pintype "unspecified"))
    )
    (net (code "71") (name "unconnected-(USB1-ID-Pad4)") (class "Default")
      (node (ref "USB1") (pin "4") (pinfunction "ID_4") (pintype "unspecified+no_connect"))
    )
  )
)
